# SX1231.net
KiCad netlist of a schematic drawn in EAGLE
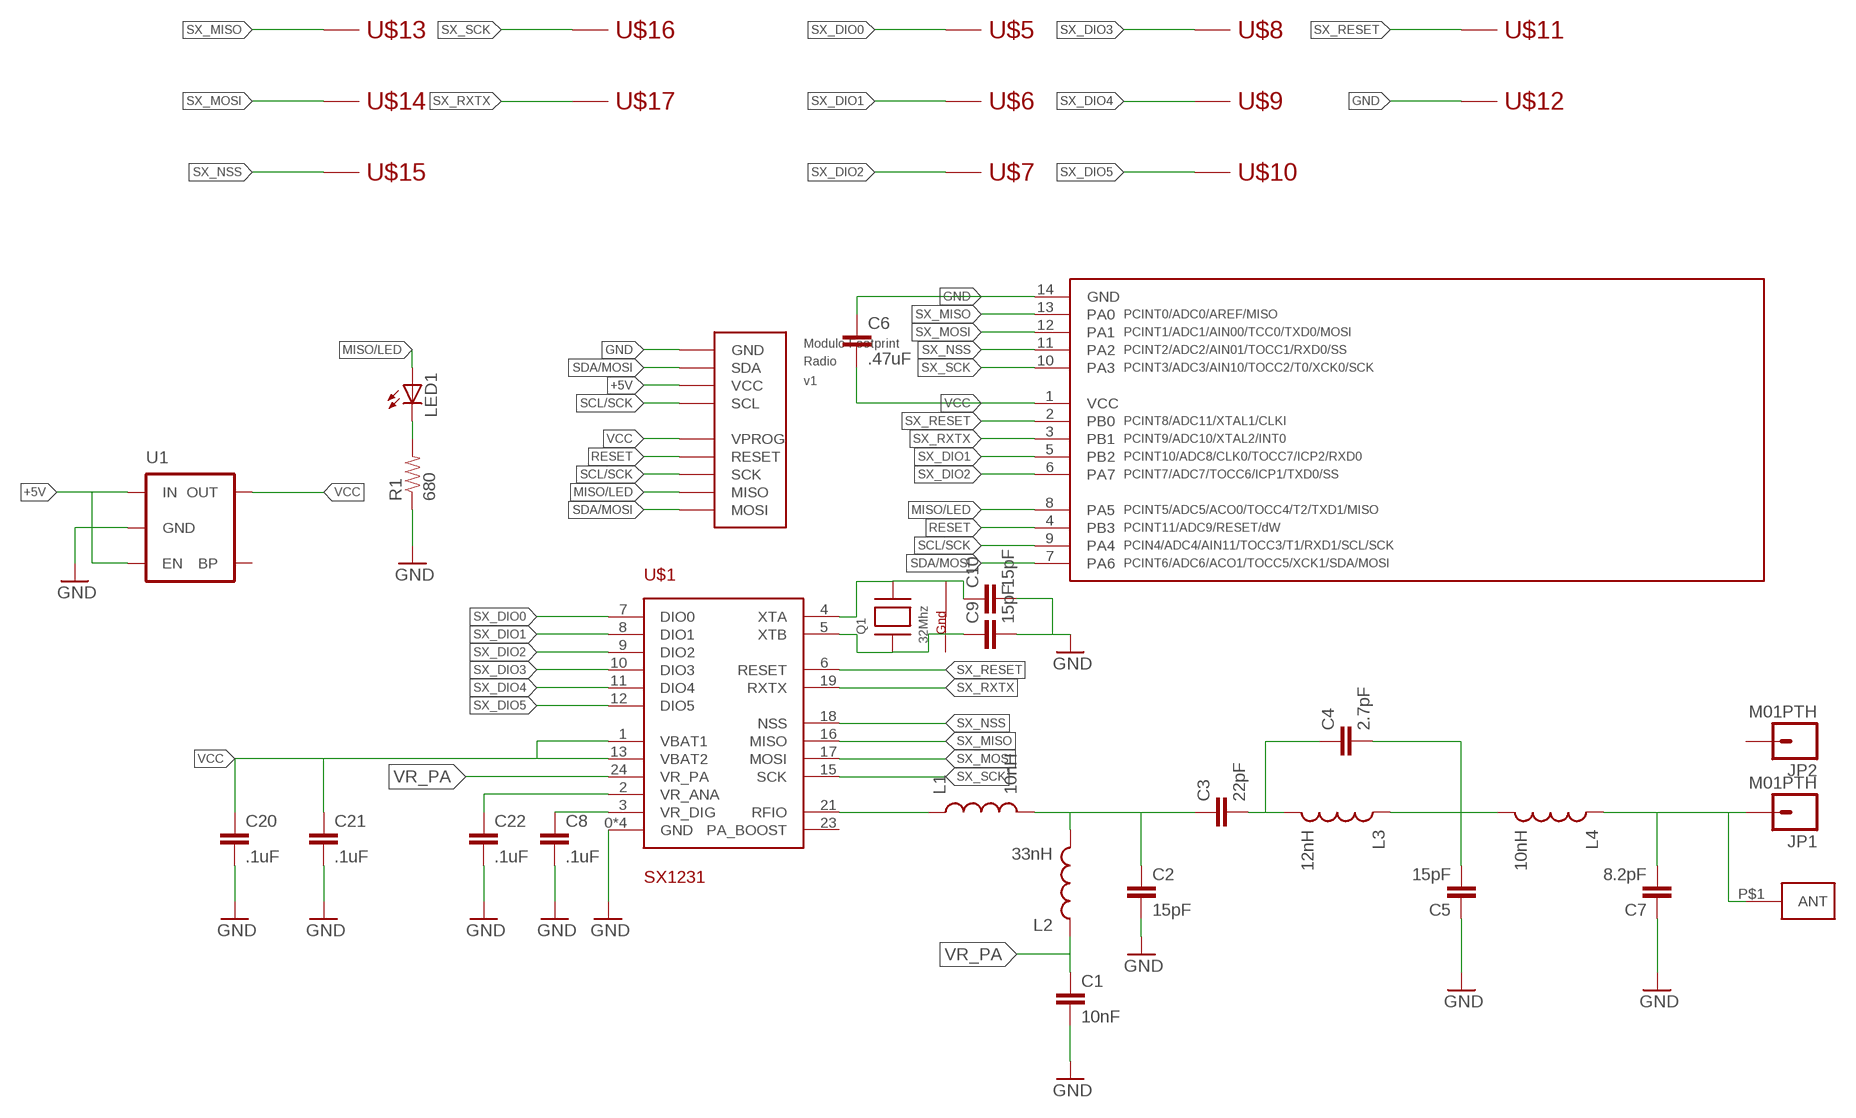
[diagram p0: schematic, sheet 1]

(export (version "E")
  (design (tool "Eeschema 10.0.6"))
  (components
    (comp (ref "C1")
      (value "10nF")
      (footprint "eagle-import:0805")
      (libsource (lib "eagle-import") (part "CAP0805"))
    )
    (comp (ref "C2")
      (value "15pF")
      (footprint "eagle-import:0805")
      (libsource (lib "eagle-import") (part "CAP0805"))
    )
    (comp (ref "C3")
      (value "22pF")
      (footprint "eagle-import:0805")
      (libsource (lib "eagle-import") (part "CAP0805"))
    )
    (comp (ref "C4")
      (value "2.7pF")
      (footprint "eagle-import:0805")
      (libsource (lib "eagle-import") (part "CAP0805"))
    )
    (comp (ref "C5")
      (value "15pF")
      (footprint "eagle-import:0805")
      (libsource (lib "eagle-import") (part "CAP0805"))
    )
    (comp (ref "C6")
      (value ".47uF")
      (footprint "eagle-import:0805")
      (libsource (lib "eagle-import") (part "CAP0805"))
    )
    (comp (ref "C7")
      (value "8.2pF")
      (footprint "eagle-import:0805")
      (libsource (lib "eagle-import") (part "CAP0805"))
    )
    (comp (ref "C8")
      (value ".1uF")
      (footprint "eagle-import:0805")
      (libsource (lib "eagle-import") (part "CAP0805"))
    )
    (comp (ref "C9")
      (value "15pF")
      (footprint "eagle-import:0805")
      (libsource (lib "eagle-import") (part "CAP0805"))
    )
    (comp (ref "C10")
      (value "15pF")
      (footprint "eagle-import:0805")
      (libsource (lib "eagle-import") (part "CAP0805"))
    )
    (comp (ref "C20")
      (value ".1uF")
      (footprint "eagle-import:0805")
      (libsource (lib "eagle-import") (part "CAP0805"))
    )
    (comp (ref "C21")
      (value ".1uF")
      (footprint "eagle-import:0805")
      (libsource (lib "eagle-import") (part "CAP0805"))
    )
    (comp (ref "C22")
      (value ".1uF")
      (footprint "eagle-import:0805")
      (libsource (lib "eagle-import") (part "CAP0805"))
    )
    (comp (ref "JP1")
      (value "M01PTH")
      (footprint "eagle-import:1X01")
      (libsource (lib "eagle-import") (part "M01PTH"))
    )
    (comp (ref "JP2")
      (value "M01PTH")
      (footprint "eagle-import:1X01")
      (libsource (lib "eagle-import") (part "M01PTH"))
    )
    (comp (ref "L1")
      (value "10nH")
      (footprint "eagle-import:0805")
      (libsource (lib "eagle-import") (part "INDUCTOR0805"))
    )
    (comp (ref "L2")
      (value "33nH")
      (footprint "eagle-import:0805")
      (libsource (lib "eagle-import") (part "INDUCTOR0805"))
    )
    (comp (ref "L3")
      (value "12nH")
      (footprint "eagle-import:0805")
      (libsource (lib "eagle-import") (part "INDUCTOR0805"))
    )
    (comp (ref "L4")
      (value "10nH")
      (footprint "eagle-import:0805")
      (libsource (lib "eagle-import") (part "INDUCTOR0805"))
    )
    (comp (ref "LED1")
      (value "LEDCHIP-LED0805")
      (footprint "eagle-import:CHIP-LED0805")
      (libsource (lib "eagle-import") (part "LEDCHIP-LED0805"))
    )
    (comp (ref "Q1")
      (value "32Mhz")
      (footprint "eagle-import:NX3225")
      (libsource (lib "eagle-import") (part "XTAL-4-3225"))
    )
    (comp (ref "R1")
      (value "680")
      (footprint "eagle-import:0805")
      (libsource (lib "eagle-import") (part "RESISTOR0805"))
    )
    (comp (ref "U$1")
      (value "SX1231")
      (footprint "eagle-import:QFN-24")
      (libsource (lib "eagle-import") (part "SX1231"))
    )
    (comp (ref "U$2")
      (value "FOOTPRINTFOOTPRINT-2")
      (footprint "eagle-import:FOOTPRINT2")
      (fields (field (name "BOARD") "Radio") (field (name "VERSION") "v1"))
      (libsource (lib "eagle-import") (part "FOOTPRINTFOOTPRINT-2"))
    )
    (comp (ref "U$3")
      (value "TINY841")
      (footprint "eagle-import:SOIC14")
      (libsource (lib "eagle-import") (part "TINY841"))
    )
    (comp (ref "U$4")
      (value "ANTENNA")
      (footprint "eagle-import:ANT-433-PW-LP")
      (libsource (lib "eagle-import") (part "ANTENNA"))
    )
    (comp (ref "U$5")
      (value "TESTPOINT")
      (footprint "eagle-import:TESTPOINT")
      (libsource (lib "eagle-import") (part "TESTPOINT"))
    )
    (comp (ref "U$6")
      (value "TESTPOINT")
      (footprint "eagle-import:TESTPOINT")
      (libsource (lib "eagle-import") (part "TESTPOINT"))
    )
    (comp (ref "U$7")
      (value "TESTPOINT")
      (footprint "eagle-import:TESTPOINT")
      (libsource (lib "eagle-import") (part "TESTPOINT"))
    )
    (comp (ref "U$8")
      (value "TESTPOINT")
      (footprint "eagle-import:TESTPOINT")
      (libsource (lib "eagle-import") (part "TESTPOINT"))
    )
    (comp (ref "U$9")
      (value "TESTPOINT")
      (footprint "eagle-import:TESTPOINT")
      (libsource (lib "eagle-import") (part "TESTPOINT"))
    )
    (comp (ref "U$10")
      (value "TESTPOINT")
      (footprint "eagle-import:TESTPOINT")
      (libsource (lib "eagle-import") (part "TESTPOINT"))
    )
    (comp (ref "U$11")
      (value "TESTPOINT")
      (footprint "eagle-import:TESTPOINT")
      (libsource (lib "eagle-import") (part "TESTPOINT"))
    )
    (comp (ref "U$12")
      (value "TESTPOINT")
      (footprint "eagle-import:TESTPOINT")
      (libsource (lib "eagle-import") (part "TESTPOINT"))
    )
    (comp (ref "U$13")
      (value "TESTPOINT")
      (footprint "eagle-import:TESTPOINT")
      (libsource (lib "eagle-import") (part "TESTPOINT"))
    )
    (comp (ref "U$14")
      (value "TESTPOINT")
      (footprint "eagle-import:TESTPOINT")
      (libsource (lib "eagle-import") (part "TESTPOINT"))
    )
    (comp (ref "U$15")
      (value "TESTPOINT")
      (footprint "eagle-import:TESTPOINT")
      (libsource (lib "eagle-import") (part "TESTPOINT"))
    )
    (comp (ref "U$16")
      (value "TESTPOINT")
      (footprint "eagle-import:TESTPOINT")
      (libsource (lib "eagle-import") (part "TESTPOINT"))
    )
    (comp (ref "U$17")
      (value "TESTPOINT")
      (footprint "eagle-import:TESTPOINT")
      (libsource (lib "eagle-import") (part "TESTPOINT"))
    )
    (comp (ref "U1")
      (value "MIC52053.3V")
      (footprint "eagle-import:SOT23-5")
      (libsource (lib "eagle-import") (part "MIC52053.3V"))
    )
  )
  (nets
    (net (code "1") (name "+5V") (class "Default")
      (node (ref "U$2") (pin "BUS2") (pinfunction "VCC_BUS2") (pintype "bidirectional"))
      (node (ref "U1") (pin "1") (pinfunction "IN_1") (pintype "input"))
      (node (ref "U1") (pin "3") (pinfunction "EN_3") (pintype "input"))
    )
    (net (code "2") (name "/G1") (class "Default")
      (node (ref "Q1") (pin "4") (pinfunction "G1_4") (pintype "power_in"))
    )
    (net (code "3") (name "/G2") (class "Default")
      (node (ref "Q1") (pin "2") (pinfunction "G2_2") (pintype "power_in"))
    )
    (net (code "4") (name "GND") (class "Default")
      (node (ref "C1") (pin "2") (pinfunction "2_2") (pintype "passive"))
      (node (ref "C10") (pin "2") (pinfunction "2_2") (pintype "passive"))
      (node (ref "C2") (pin "2") (pinfunction "2_2") (pintype "passive"))
      (node (ref "C20") (pin "2") (pinfunction "2_2") (pintype "passive"))
      (node (ref "C21") (pin "2") (pinfunction "2_2") (pintype "passive"))
      (node (ref "C22") (pin "2") (pinfunction "2_2") (pintype "passive"))
      (node (ref "C5") (pin "1") (pinfunction "1_1") (pintype "passive"))
      (node (ref "C6") (pin "1") (pinfunction "1_1") (pintype "passive"))
      (node (ref "C7") (pin "1") (pinfunction "1_1") (pintype "passive"))
      (node (ref "C8") (pin "2") (pinfunction "2_2") (pintype "passive"))
      (node (ref "C9") (pin "2") (pinfunction "2_2") (pintype "passive"))
      (node (ref "R1") (pin "1") (pinfunction "1_1") (pintype "passive"))
      (node (ref "U$1") (pin "0") (pinfunction "GND_0") (pintype "bidirectional"))
      (node (ref "U$1") (pin "14") (pinfunction "GND_14") (pintype "bidirectional"))
      (node (ref "U$1") (pin "20") (pinfunction "GND_20") (pintype "bidirectional"))
      (node (ref "U$1") (pin "22") (pinfunction "GND_22") (pintype "bidirectional"))
      (node (ref "U$12") (pin "P$1") (pinfunction "1_P$1") (pintype "bidirectional"))
      (node (ref "U$2") (pin "BUS0") (pinfunction "GND_BUS0") (pintype "bidirectional"))
      (node (ref "U$3") (pin "14") (pinfunction "GND_14") (pintype "bidirectional"))
      (node (ref "U1") (pin "2") (pinfunction "GND_2") (pintype "input"))
    )
    (net (code "5") (name "MISO{slash}LED") (class "Default")
      (node (ref "LED1") (pin "A") (pinfunction "A_A") (pintype "passive"))
      (node (ref "U$2") (pin "PROG3") (pinfunction "MISO_PROG3") (pintype "bidirectional"))
      (node (ref "U$3") (pin "8") (pinfunction "PA5_8") (pintype "bidirectional"))
    )
    (net (code "6") (name "Net-(C2-Pad1)") (class "Default")
      (node (ref "C2") (pin "1") (pinfunction "1_1") (pintype "passive"))
      (node (ref "C3") (pin "1") (pinfunction "1_1") (pintype "passive"))
      (node (ref "L1") (pin "2") (pinfunction "2_2") (pintype "passive"))
      (node (ref "L2") (pin "2") (pinfunction "2_2") (pintype "passive"))
    )
    (net (code "7") (name "Net-(C3-Pad2)") (class "Default")
      (node (ref "C3") (pin "2") (pinfunction "2_2") (pintype "passive"))
      (node (ref "C4") (pin "1") (pinfunction "1_1") (pintype "passive"))
      (node (ref "L3") (pin "2") (pinfunction "2_2") (pintype "passive"))
    )
    (net (code "8") (name "Net-(C4-Pad2)") (class "Default")
      (node (ref "C4") (pin "2") (pinfunction "2_2") (pintype "passive"))
      (node (ref "C5") (pin "2") (pinfunction "2_2") (pintype "passive"))
      (node (ref "L3") (pin "1") (pinfunction "1_1") (pintype "passive"))
      (node (ref "L4") (pin "2") (pinfunction "2_2") (pintype "passive"))
    )
    (net (code "9") (name "Net-(LED1-PadC)") (class "Default")
      (node (ref "LED1") (pin "C") (pinfunction "C_C") (pintype "passive"))
      (node (ref "R1") (pin "2") (pinfunction "2_2") (pintype "passive"))
    )
    (net (code "10") (name "Net-(Q1-X1)") (class "Default")
      (node (ref "C9") (pin "1") (pinfunction "1_1") (pintype "passive"))
      (node (ref "Q1") (pin "1") (pinfunction "X1_1") (pintype "bidirectional"))
      (node (ref "U$1") (pin "5") (pinfunction "XTB_5") (pintype "bidirectional"))
    )
    (net (code "11") (name "Net-(Q1-X2)") (class "Default")
      (node (ref "C10") (pin "1") (pinfunction "1_1") (pintype "passive"))
      (node (ref "Q1") (pin "3") (pinfunction "X2_3") (pintype "bidirectional"))
      (node (ref "U$1") (pin "4") (pinfunction "XTA_4") (pintype "bidirectional"))
    )
    (net (code "12") (name "Net-(U$1-RFIO)") (class "Default")
      (node (ref "L1") (pin "1") (pinfunction "1_1") (pintype "passive"))
      (node (ref "U$1") (pin "21") (pinfunction "RFIO_21") (pintype "bidirectional"))
    )
    (net (code "13") (name "Net-(U$1-VR_ANA)") (class "Default")
      (node (ref "C22") (pin "1") (pinfunction "1_1") (pintype "passive"))
      (node (ref "U$1") (pin "2") (pinfunction "VR_ANA_2") (pintype "bidirectional"))
    )
    (net (code "14") (name "Net-(U$1-VR_DIG)") (class "Default")
      (node (ref "C8") (pin "1") (pinfunction "1_1") (pintype "passive"))
      (node (ref "U$1") (pin "3") (pinfunction "VR_DIG_3") (pintype "bidirectional"))
    )
    (net (code "15") (name "Net-(U$4-ANT)") (class "Default")
      (node (ref "C7") (pin "2") (pinfunction "2_2") (pintype "passive"))
      (node (ref "JP1") (pin "1") (pinfunction "1_1") (pintype "passive"))
      (node (ref "L4") (pin "1") (pinfunction "1_1") (pintype "passive"))
      (node (ref "U$4") (pin "P$1") (pinfunction "ANT_P$1") (pintype "bidirectional"))
    )
    (net (code "16") (name "RESET") (class "Default")
      (node (ref "U$2") (pin "PROG1") (pinfunction "RESET_PROG1") (pintype "bidirectional"))
      (node (ref "U$3") (pin "4") (pinfunction "PB3_4") (pintype "bidirectional"))
    )
    (net (code "17") (name "SCL{slash}SCK") (class "Default")
      (node (ref "U$2") (pin "BUS3") (pinfunction "SCL_BUS3") (pintype "bidirectional"))
      (node (ref "U$2") (pin "PROG2") (pinfunction "SCK_PROG2") (pintype "bidirectional"))
      (node (ref "U$3") (pin "9") (pinfunction "PA4_9") (pintype "bidirectional"))
    )
    (net (code "18") (name "SDA{slash}MOSI") (class "Default")
      (node (ref "U$2") (pin "BUS1") (pinfunction "SDA_BUS1") (pintype "bidirectional"))
      (node (ref "U$2") (pin "PROG4") (pinfunction "MOSI_PROG4") (pintype "bidirectional"))
      (node (ref "U$3") (pin "7") (pinfunction "PA6_7") (pintype "bidirectional"))
    )
    (net (code "19") (name "SX_DIO0") (class "Default")
      (node (ref "U$1") (pin "7") (pinfunction "DIO0_7") (pintype "bidirectional"))
      (node (ref "U$5") (pin "P$1") (pinfunction "1_P$1") (pintype "bidirectional"))
    )
    (net (code "20") (name "SX_DIO1") (class "Default")
      (node (ref "U$1") (pin "8") (pinfunction "DIO1_8") (pintype "bidirectional"))
      (node (ref "U$3") (pin "5") (pinfunction "PB2_5") (pintype "bidirectional"))
      (node (ref "U$6") (pin "P$1") (pinfunction "1_P$1") (pintype "bidirectional"))
    )
    (net (code "21") (name "SX_DIO2") (class "Default")
      (node (ref "U$1") (pin "9") (pinfunction "DIO2_9") (pintype "bidirectional"))
      (node (ref "U$3") (pin "6") (pinfunction "PA7_6") (pintype "bidirectional"))
      (node (ref "U$7") (pin "P$1") (pinfunction "1_P$1") (pintype "bidirectional"))
    )
    (net (code "22") (name "SX_DIO3") (class "Default")
      (node (ref "U$1") (pin "10") (pinfunction "DIO3_10") (pintype "bidirectional"))
      (node (ref "U$8") (pin "P$1") (pinfunction "1_P$1") (pintype "bidirectional"))
    )
    (net (code "23") (name "SX_DIO4") (class "Default")
      (node (ref "U$1") (pin "11") (pinfunction "DIO4_11") (pintype "bidirectional"))
      (node (ref "U$9") (pin "P$1") (pinfunction "1_P$1") (pintype "bidirectional"))
    )
    (net (code "24") (name "SX_DIO5") (class "Default")
      (node (ref "U$1") (pin "12") (pinfunction "DIO5_12") (pintype "bidirectional"))
      (node (ref "U$10") (pin "P$1") (pinfunction "1_P$1") (pintype "bidirectional"))
    )
    (net (code "25") (name "SX_MISO") (class "Default")
      (node (ref "U$1") (pin "16") (pinfunction "MISO_16") (pintype "bidirectional"))
      (node (ref "U$13") (pin "P$1") (pinfunction "1_P$1") (pintype "bidirectional"))
      (node (ref "U$3") (pin "13") (pinfunction "PA0_13") (pintype "bidirectional"))
    )
    (net (code "26") (name "SX_MOSI") (class "Default")
      (node (ref "U$1") (pin "17") (pinfunction "MOSI_17") (pintype "bidirectional"))
      (node (ref "U$14") (pin "P$1") (pinfunction "1_P$1") (pintype "bidirectional"))
      (node (ref "U$3") (pin "12") (pinfunction "PA1_12") (pintype "bidirectional"))
    )
    (net (code "27") (name "SX_NSS") (class "Default")
      (node (ref "U$1") (pin "18") (pinfunction "NSS_18") (pintype "bidirectional"))
      (node (ref "U$15") (pin "P$1") (pinfunction "1_P$1") (pintype "bidirectional"))
      (node (ref "U$3") (pin "11") (pinfunction "PA2_11") (pintype "bidirectional"))
    )
    (net (code "28") (name "SX_RESET") (class "Default")
      (node (ref "U$1") (pin "6") (pinfunction "RESET_6") (pintype "bidirectional"))
      (node (ref "U$11") (pin "P$1") (pinfunction "1_P$1") (pintype "bidirectional"))
      (node (ref "U$3") (pin "2") (pinfunction "PB0_2") (pintype "bidirectional"))
    )
    (net (code "29") (name "SX_RXTX") (class "Default")
      (node (ref "U$1") (pin "19") (pinfunction "RXTX_19") (pintype "bidirectional"))
      (node (ref "U$17") (pin "P$1") (pinfunction "1_P$1") (pintype "bidirectional"))
      (node (ref "U$3") (pin "3") (pinfunction "PB1_3") (pintype "bidirectional"))
    )
    (net (code "30") (name "SX_SCK") (class "Default")
      (node (ref "U$1") (pin "15") (pinfunction "SCK_15") (pintype "bidirectional"))
      (node (ref "U$16") (pin "P$1") (pinfunction "1_P$1") (pintype "bidirectional"))
      (node (ref "U$3") (pin "10") (pinfunction "PA3_10") (pintype "bidirectional"))
    )
    (net (code "31") (name "VCC") (class "Default")
      (node (ref "C20") (pin "1") (pinfunction "1_1") (pintype "passive"))
      (node (ref "C21") (pin "1") (pinfunction "1_1") (pintype "passive"))
      (node (ref "C6") (pin "2") (pinfunction "2_2") (pintype "passive"))
      (node (ref "U$1") (pin "1") (pinfunction "VBAT1_1") (pintype "bidirectional"))
      (node (ref "U$1") (pin "13") (pinfunction "VBAT2_13") (pintype "bidirectional"))
      (node (ref "U$2") (pin "PROG0") (pinfunction "VPROG_PROG0") (pintype "bidirectional"))
      (node (ref "U$3") (pin "1") (pinfunction "VCC_1") (pintype "bidirectional"))
      (node (ref "U1") (pin "5") (pinfunction "OUT_5") (pintype "passive"))
    )
    (net (code "32") (name "VR_PA") (class "Default")
      (node (ref "C1") (pin "1") (pinfunction "1_1") (pintype "passive"))
      (node (ref "L2") (pin "1") (pinfunction "1_1") (pintype "passive"))
      (node (ref "U$1") (pin "24") (pinfunction "VR_PA_24") (pintype "bidirectional"))
    )
    (net (code "33") (name "unconnected-(JP2-Pad1)") (class "Default")
      (node (ref "JP2") (pin "1") (pinfunction "1_1") (pintype "passive"))
    )
    (net (code "34") (name "unconnected-(U$1-PA_BOOST-Pad23)") (class "Default")
      (node (ref "U$1") (pin "23") (pinfunction "PA_BOOST_23") (pintype "bidirectional"))
    )
    (net (code "35") (name "unconnected-(U1-BP-Pad4)") (class "Default")
      (node (ref "U1") (pin "4") (pinfunction "BP_4") (pintype "input"))
    )
  )
)
